# Displays.net
KiCad netlist of a schematic drawn in Altium Designer
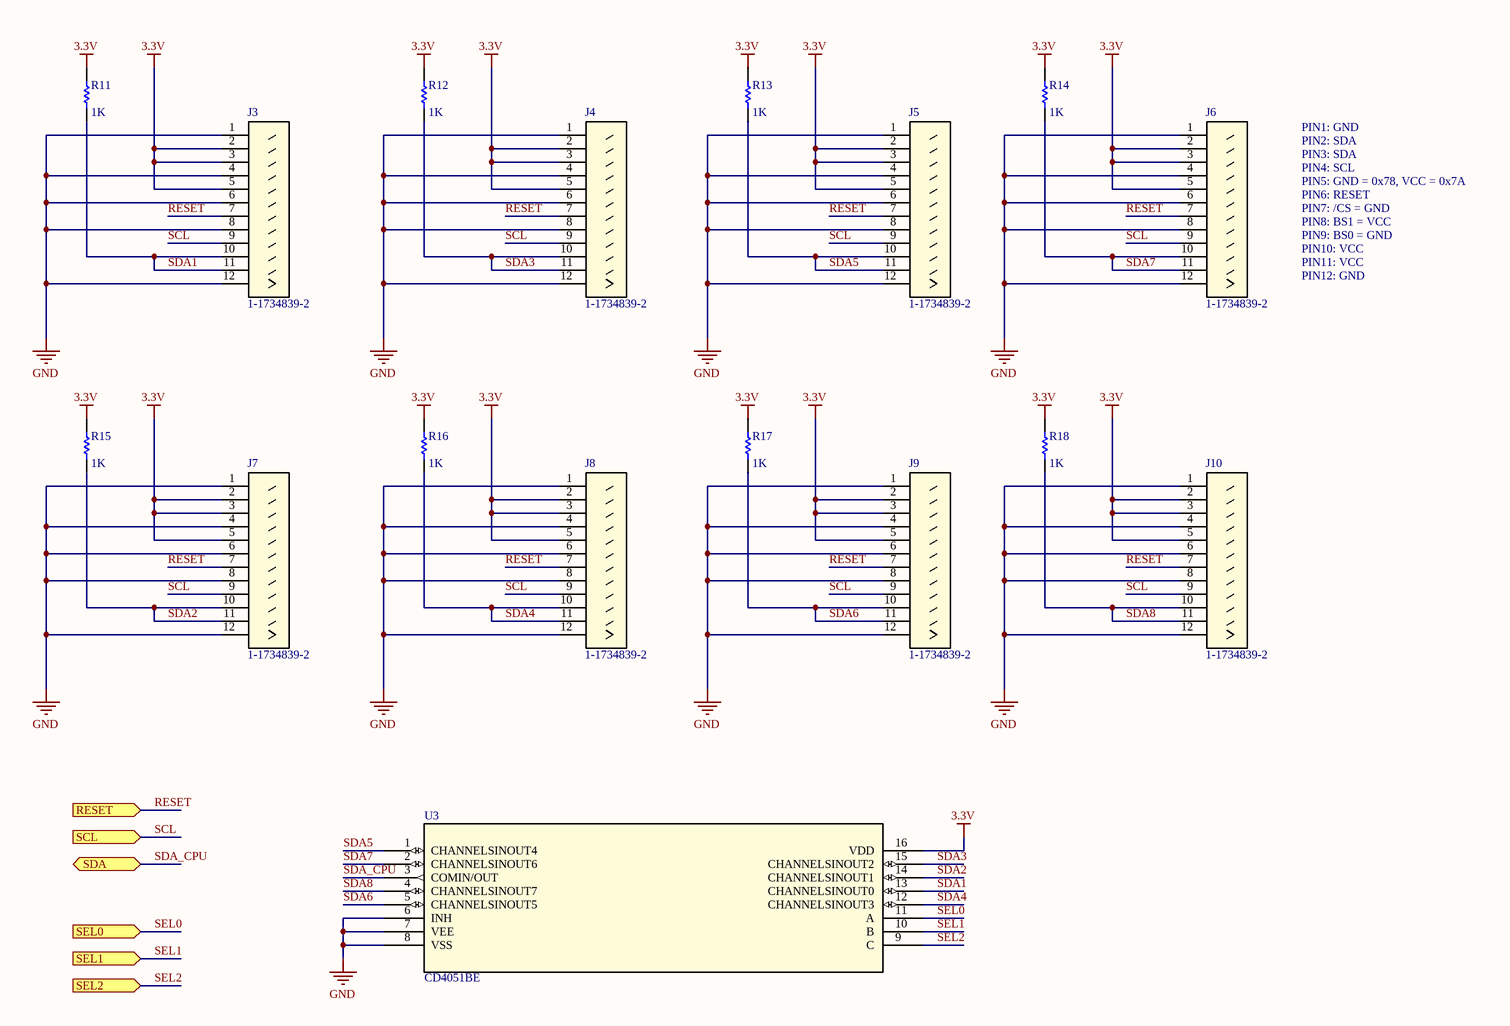
[diagram p0: Displays.SchDoc]

(export (version "E")
  (design (tool "Eeschema 10.0.6"))
  (components
    (comp (ref "J3")
      (value "1-1734839-2")
      (footprint "CONN_1-1734592-2")
      (description "Imported")
      (fields
        (field (name "RS_PART_NUMBER") "7188674")
        (field (name "COPYRIGHT") "Copyright (C) 2015 Accelerated Designs. All rights reserved")
      )
      (libsource (lib "Zif") (part "1-1734839-2"))
    )
    (comp (ref "J4")
      (value "1-1734839-2")
      (footprint "CONN_1-1734592-2")
      (description "Imported")
      (fields
        (field (name "RS_PART_NUMBER") "7188674")
        (field (name "COPYRIGHT") "Copyright (C) 2015 Accelerated Designs. All rights reserved")
      )
      (libsource (lib "Zif") (part "1-1734839-2"))
    )
    (comp (ref "J5")
      (value "1-1734839-2")
      (footprint "CONN_1-1734592-2")
      (description "Imported")
      (fields
        (field (name "RS_PART_NUMBER") "7188674")
        (field (name "COPYRIGHT") "Copyright (C) 2015 Accelerated Designs. All rights reserved")
      )
      (libsource (lib "Zif") (part "1-1734839-2"))
    )
    (comp (ref "J6")
      (value "1-1734839-2")
      (footprint "CONN_1-1734592-2")
      (description "Imported")
      (fields
        (field (name "RS_PART_NUMBER") "7188674")
        (field (name "COPYRIGHT") "Copyright (C) 2015 Accelerated Designs. All rights reserved")
      )
      (libsource (lib "Zif") (part "1-1734839-2"))
    )
    (comp (ref "J7")
      (value "1-1734839-2")
      (footprint "CONN_1-1734592-2")
      (description "Imported")
      (fields
        (field (name "RS_PART_NUMBER") "7188674")
        (field (name "COPYRIGHT") "Copyright (C) 2015 Accelerated Designs. All rights reserved")
      )
      (libsource (lib "Zif") (part "1-1734839-2"))
    )
    (comp (ref "J8")
      (value "1-1734839-2")
      (footprint "CONN_1-1734592-2")
      (description "Imported")
      (fields
        (field (name "RS_PART_NUMBER") "7188674")
        (field (name "COPYRIGHT") "Copyright (C) 2015 Accelerated Designs. All rights reserved")
      )
      (libsource (lib "Zif") (part "1-1734839-2"))
    )
    (comp (ref "J9")
      (value "1-1734839-2")
      (footprint "CONN_1-1734592-2")
      (description "Imported")
      (fields
        (field (name "RS_PART_NUMBER") "7188674")
        (field (name "COPYRIGHT") "Copyright (C) 2015 Accelerated Designs. All rights reserved")
      )
      (libsource (lib "Zif") (part "1-1734839-2"))
    )
    (comp (ref "J10")
      (value "1-1734839-2")
      (footprint "CONN_1-1734592-2")
      (description "Imported")
      (fields
        (field (name "RS_PART_NUMBER") "7188674")
        (field (name "COPYRIGHT") "Copyright (C) 2015 Accelerated Designs. All rights reserved")
      )
      (libsource (lib "Zif") (part "1-1734839-2"))
    )
    (comp (ref "R11")
      (value "1K")
      (footprint "6-0805_N")
      (description "Resistor")
      (fields (field (name "PUBLISHER") "Altium Limited"))
      (libsource (lib "Miscellaneous Devices") (part "Res1"))
    )
    (comp (ref "R12")
      (value "1K")
      (footprint "6-0805_N")
      (description "Resistor")
      (fields (field (name "PUBLISHER") "Altium Limited"))
      (libsource (lib "Miscellaneous Devices") (part "Res1"))
    )
    (comp (ref "R13")
      (value "1K")
      (footprint "6-0805_N")
      (description "Resistor")
      (fields (field (name "PUBLISHER") "Altium Limited"))
      (libsource (lib "Miscellaneous Devices") (part "Res1"))
    )
    (comp (ref "R14")
      (value "1K")
      (footprint "6-0805_N")
      (description "Resistor")
      (fields (field (name "PUBLISHER") "Altium Limited"))
      (libsource (lib "Miscellaneous Devices") (part "Res1"))
    )
    (comp (ref "R15")
      (value "1K")
      (footprint "6-0805_N")
      (description "Resistor")
      (fields (field (name "PUBLISHER") "Altium Limited"))
      (libsource (lib "Miscellaneous Devices") (part "Res1"))
    )
    (comp (ref "R16")
      (value "1K")
      (footprint "6-0805_N")
      (description "Resistor")
      (fields (field (name "PUBLISHER") "Altium Limited"))
      (libsource (lib "Miscellaneous Devices") (part "Res1"))
    )
    (comp (ref "R17")
      (value "1K")
      (footprint "6-0805_N")
      (description "Resistor")
      (fields (field (name "PUBLISHER") "Altium Limited"))
      (libsource (lib "Miscellaneous Devices") (part "Res1"))
    )
    (comp (ref "R18")
      (value "1K")
      (footprint "6-0805_N")
      (description "Resistor")
      (fields (field (name "PUBLISHER") "Altium Limited"))
      (libsource (lib "Miscellaneous Devices") (part "Res1"))
    )
    (comp (ref "U3")
      (value "CD4051BE")
      (footprint "N16")
      (description "Imported")
      (fields
        (field (name "RS_PART_NUMBER") "5036098")
        (field (name "COPYRIGHT") "Copyright (C) 2015 Accelerated Designs. All rights reserved")
      )
      (libsource (lib "display_mux") (part "CD4051BE"))
    )
  )
  (nets
    (net (code "1") (name "/RESET") (class "Default")
      (node (ref "J10") (pin "7") (pinfunction "7_7") (pintype "passive"))
      (node (ref "J3") (pin "7") (pinfunction "7_7") (pintype "passive"))
      (node (ref "J4") (pin "7") (pinfunction "7_7") (pintype "passive"))
      (node (ref "J5") (pin "7") (pinfunction "7_7") (pintype "passive"))
      (node (ref "J6") (pin "7") (pinfunction "7_7") (pintype "passive"))
      (node (ref "J7") (pin "7") (pinfunction "7_7") (pintype "passive"))
      (node (ref "J8") (pin "7") (pinfunction "7_7") (pintype "passive"))
      (node (ref "J9") (pin "7") (pinfunction "7_7") (pintype "passive"))
    )
    (net (code "2") (name "/SCL") (class "Default")
      (node (ref "J10") (pin "9") (pinfunction "9_9") (pintype "passive"))
      (node (ref "J3") (pin "9") (pinfunction "9_9") (pintype "passive"))
      (node (ref "J4") (pin "9") (pinfunction "9_9") (pintype "passive"))
      (node (ref "J5") (pin "9") (pinfunction "9_9") (pintype "passive"))
      (node (ref "J6") (pin "9") (pinfunction "9_9") (pintype "passive"))
      (node (ref "J7") (pin "9") (pinfunction "9_9") (pintype "passive"))
      (node (ref "J8") (pin "9") (pinfunction "9_9") (pintype "passive"))
      (node (ref "J9") (pin "9") (pinfunction "9_9") (pintype "passive"))
    )
    (net (code "3") (name "/SDA1") (class "Default")
      (node (ref "J3") (pin "10") (pinfunction "10_10") (pintype "passive"))
      (node (ref "J3") (pin "11") (pinfunction "11_11") (pintype "passive"))
      (node (ref "R11") (pin "2") (pinfunction "2_2") (pintype "passive"))
      (node (ref "U3") (pin "13") (pinfunction "CHANNELSINOUT0_13") (pintype "bidirectional"))
    )
    (net (code "4") (name "/SDA2") (class "Default")
      (node (ref "J7") (pin "10") (pinfunction "10_10") (pintype "passive"))
      (node (ref "J7") (pin "11") (pinfunction "11_11") (pintype "passive"))
      (node (ref "R15") (pin "2") (pinfunction "2_2") (pintype "passive"))
      (node (ref "U3") (pin "14") (pinfunction "CHANNELSINOUT1_14") (pintype "bidirectional"))
    )
    (net (code "5") (name "/SDA3") (class "Default")
      (node (ref "J4") (pin "10") (pinfunction "10_10") (pintype "passive"))
      (node (ref "J4") (pin "11") (pinfunction "11_11") (pintype "passive"))
      (node (ref "R12") (pin "2") (pinfunction "2_2") (pintype "passive"))
      (node (ref "U3") (pin "15") (pinfunction "CHANNELSINOUT2_15") (pintype "bidirectional"))
    )
    (net (code "6") (name "/SDA4") (class "Default")
      (node (ref "J8") (pin "10") (pinfunction "10_10") (pintype "passive"))
      (node (ref "J8") (pin "11") (pinfunction "11_11") (pintype "passive"))
      (node (ref "R16") (pin "2") (pinfunction "2_2") (pintype "passive"))
      (node (ref "U3") (pin "12") (pinfunction "CHANNELSINOUT3_12") (pintype "bidirectional"))
    )
    (net (code "7") (name "/SDA5") (class "Default")
      (node (ref "J5") (pin "10") (pinfunction "10_10") (pintype "passive"))
      (node (ref "J5") (pin "11") (pinfunction "11_11") (pintype "passive"))
      (node (ref "R13") (pin "2") (pinfunction "2_2") (pintype "passive"))
      (node (ref "U3") (pin "1") (pinfunction "CHANNELSINOUT4_1") (pintype "bidirectional"))
    )
    (net (code "8") (name "/SDA6") (class "Default")
      (node (ref "J9") (pin "10") (pinfunction "10_10") (pintype "passive"))
      (node (ref "J9") (pin "11") (pinfunction "11_11") (pintype "passive"))
      (node (ref "R17") (pin "2") (pinfunction "2_2") (pintype "passive"))
      (node (ref "U3") (pin "5") (pinfunction "CHANNELSINOUT5_5") (pintype "bidirectional"))
    )
    (net (code "9") (name "/SDA7") (class "Default")
      (node (ref "J6") (pin "10") (pinfunction "10_10") (pintype "passive"))
      (node (ref "J6") (pin "11") (pinfunction "11_11") (pintype "passive"))
      (node (ref "R14") (pin "2") (pinfunction "2_2") (pintype "passive"))
      (node (ref "U3") (pin "2") (pinfunction "CHANNELSINOUT6_2") (pintype "bidirectional"))
    )
    (net (code "10") (name "/SDA8") (class "Default")
      (node (ref "J10") (pin "10") (pinfunction "10_10") (pintype "passive"))
      (node (ref "J10") (pin "11") (pinfunction "11_11") (pintype "passive"))
      (node (ref "R18") (pin "2") (pinfunction "2_2") (pintype "passive"))
      (node (ref "U3") (pin "4") (pinfunction "CHANNELSINOUT7_4") (pintype "bidirectional"))
    )
    (net (code "11") (name "/SDA_CPU") (class "Default")
      (node (ref "U3") (pin "3") (pinfunction "COMIN/OUT_3") (pintype "output"))
    )
    (net (code "12") (name "/SEL0") (class "Default")
      (node (ref "U3") (pin "11") (pinfunction "A_11") (pintype "passive"))
    )
    (net (code "13") (name "/SEL1") (class "Default")
      (node (ref "U3") (pin "10") (pinfunction "B_10") (pintype "passive"))
    )
    (net (code "14") (name "/SEL2") (class "Default")
      (node (ref "U3") (pin "9") (pinfunction "C_9") (pintype "passive"))
    )
    (net (code "15") (name "3.3V") (class "Default")
      (node (ref "J10") (pin "2") (pinfunction "2_2") (pintype "passive"))
      (node (ref "J10") (pin "3") (pinfunction "3_3") (pintype "passive"))
      (node (ref "J10") (pin "5") (pinfunction "5_5") (pintype "passive"))
      (node (ref "J3") (pin "2") (pinfunction "2_2") (pintype "passive"))
      (node (ref "J3") (pin "3") (pinfunction "3_3") (pintype "passive"))
      (node (ref "J3") (pin "5") (pinfunction "5_5") (pintype "passive"))
      (node (ref "J4") (pin "2") (pinfunction "2_2") (pintype "passive"))
      (node (ref "J4") (pin "3") (pinfunction "3_3") (pintype "passive"))
      (node (ref "J4") (pin "5") (pinfunction "5_5") (pintype "passive"))
      (node (ref "J5") (pin "2") (pinfunction "2_2") (pintype "passive"))
      (node (ref "J5") (pin "3") (pinfunction "3_3") (pintype "passive"))
      (node (ref "J5") (pin "5") (pinfunction "5_5") (pintype "passive"))
      (node (ref "J6") (pin "2") (pinfunction "2_2") (pintype "passive"))
      (node (ref "J6") (pin "3") (pinfunction "3_3") (pintype "passive"))
      (node (ref "J6") (pin "5") (pinfunction "5_5") (pintype "passive"))
      (node (ref "J7") (pin "2") (pinfunction "2_2") (pintype "passive"))
      (node (ref "J7") (pin "3") (pinfunction "3_3") (pintype "passive"))
      (node (ref "J7") (pin "5") (pinfunction "5_5") (pintype "passive"))
      (node (ref "J8") (pin "2") (pinfunction "2_2") (pintype "passive"))
      (node (ref "J8") (pin "3") (pinfunction "3_3") (pintype "passive"))
      (node (ref "J8") (pin "5") (pinfunction "5_5") (pintype "passive"))
      (node (ref "J9") (pin "2") (pinfunction "2_2") (pintype "passive"))
      (node (ref "J9") (pin "3") (pinfunction "3_3") (pintype "passive"))
      (node (ref "J9") (pin "5") (pinfunction "5_5") (pintype "passive"))
      (node (ref "R11") (pin "1") (pinfunction "1_1") (pintype "passive"))
      (node (ref "R12") (pin "1") (pinfunction "1_1") (pintype "passive"))
      (node (ref "R13") (pin "1") (pinfunction "1_1") (pintype "passive"))
      (node (ref "R14") (pin "1") (pinfunction "1_1") (pintype "passive"))
      (node (ref "R15") (pin "1") (pinfunction "1_1") (pintype "passive"))
      (node (ref "R16") (pin "1") (pinfunction "1_1") (pintype "passive"))
      (node (ref "R17") (pin "1") (pinfunction "1_1") (pintype "passive"))
      (node (ref "R18") (pin "1") (pinfunction "1_1") (pintype "passive"))
      (node (ref "U3") (pin "16") (pinfunction "VDD_16") (pintype "power_in"))
    )
    (net (code "16") (name "GND") (class "Default")
      (node (ref "J10") (pin "1") (pinfunction "1_1") (pintype "passive"))
      (node (ref "J10") (pin "12") (pinfunction "12_12") (pintype "passive"))
      (node (ref "J10") (pin "4") (pinfunction "4_4") (pintype "passive"))
      (node (ref "J10") (pin "6") (pinfunction "6_6") (pintype "passive"))
      (node (ref "J10") (pin "8") (pinfunction "8_8") (pintype "passive"))
      (node (ref "J3") (pin "1") (pinfunction "1_1") (pintype "passive"))
      (node (ref "J3") (pin "12") (pinfunction "12_12") (pintype "passive"))
      (node (ref "J3") (pin "4") (pinfunction "4_4") (pintype "passive"))
      (node (ref "J3") (pin "6") (pinfunction "6_6") (pintype "passive"))
      (node (ref "J3") (pin "8") (pinfunction "8_8") (pintype "passive"))
      (node (ref "J4") (pin "1") (pinfunction "1_1") (pintype "passive"))
      (node (ref "J4") (pin "12") (pinfunction "12_12") (pintype "passive"))
      (node (ref "J4") (pin "4") (pinfunction "4_4") (pintype "passive"))
      (node (ref "J4") (pin "6") (pinfunction "6_6") (pintype "passive"))
      (node (ref "J4") (pin "8") (pinfunction "8_8") (pintype "passive"))
      (node (ref "J5") (pin "1") (pinfunction "1_1") (pintype "passive"))
      (node (ref "J5") (pin "12") (pinfunction "12_12") (pintype "passive"))
      (node (ref "J5") (pin "4") (pinfunction "4_4") (pintype "passive"))
      (node (ref "J5") (pin "6") (pinfunction "6_6") (pintype "passive"))
      (node (ref "J5") (pin "8") (pinfunction "8_8") (pintype "passive"))
      (node (ref "J6") (pin "1") (pinfunction "1_1") (pintype "passive"))
      (node (ref "J6") (pin "12") (pinfunction "12_12") (pintype "passive"))
      (node (ref "J6") (pin "4") (pinfunction "4_4") (pintype "passive"))
      (node (ref "J6") (pin "6") (pinfunction "6_6") (pintype "passive"))
      (node (ref "J6") (pin "8") (pinfunction "8_8") (pintype "passive"))
      (node (ref "J7") (pin "1") (pinfunction "1_1") (pintype "passive"))
      (node (ref "J7") (pin "12") (pinfunction "12_12") (pintype "passive"))
      (node (ref "J7") (pin "4") (pinfunction "4_4") (pintype "passive"))
      (node (ref "J7") (pin "6") (pinfunction "6_6") (pintype "passive"))
      (node (ref "J7") (pin "8") (pinfunction "8_8") (pintype "passive"))
      (node (ref "J8") (pin "1") (pinfunction "1_1") (pintype "passive"))
      (node (ref "J8") (pin "12") (pinfunction "12_12") (pintype "passive"))
      (node (ref "J8") (pin "4") (pinfunction "4_4") (pintype "passive"))
      (node (ref "J8") (pin "6") (pinfunction "6_6") (pintype "passive"))
      (node (ref "J8") (pin "8") (pinfunction "8_8") (pintype "passive"))
      (node (ref "J9") (pin "1") (pinfunction "1_1") (pintype "passive"))
      (node (ref "J9") (pin "12") (pinfunction "12_12") (pintype "passive"))
      (node (ref "J9") (pin "4") (pinfunction "4_4") (pintype "passive"))
      (node (ref "J9") (pin "6") (pinfunction "6_6") (pintype "passive"))
      (node (ref "J9") (pin "8") (pinfunction "8_8") (pintype "passive"))
      (node (ref "U3") (pin "6") (pinfunction "INH_6") (pintype "passive"))
      (node (ref "U3") (pin "7") (pinfunction "VEE_7") (pintype "power_in"))
      (node (ref "U3") (pin "8") (pinfunction "VSS_8") (pintype "power_in"))
    )
  )
)
